# p2-003.net
KiCad netlist of a schematic drawn in EAGLE
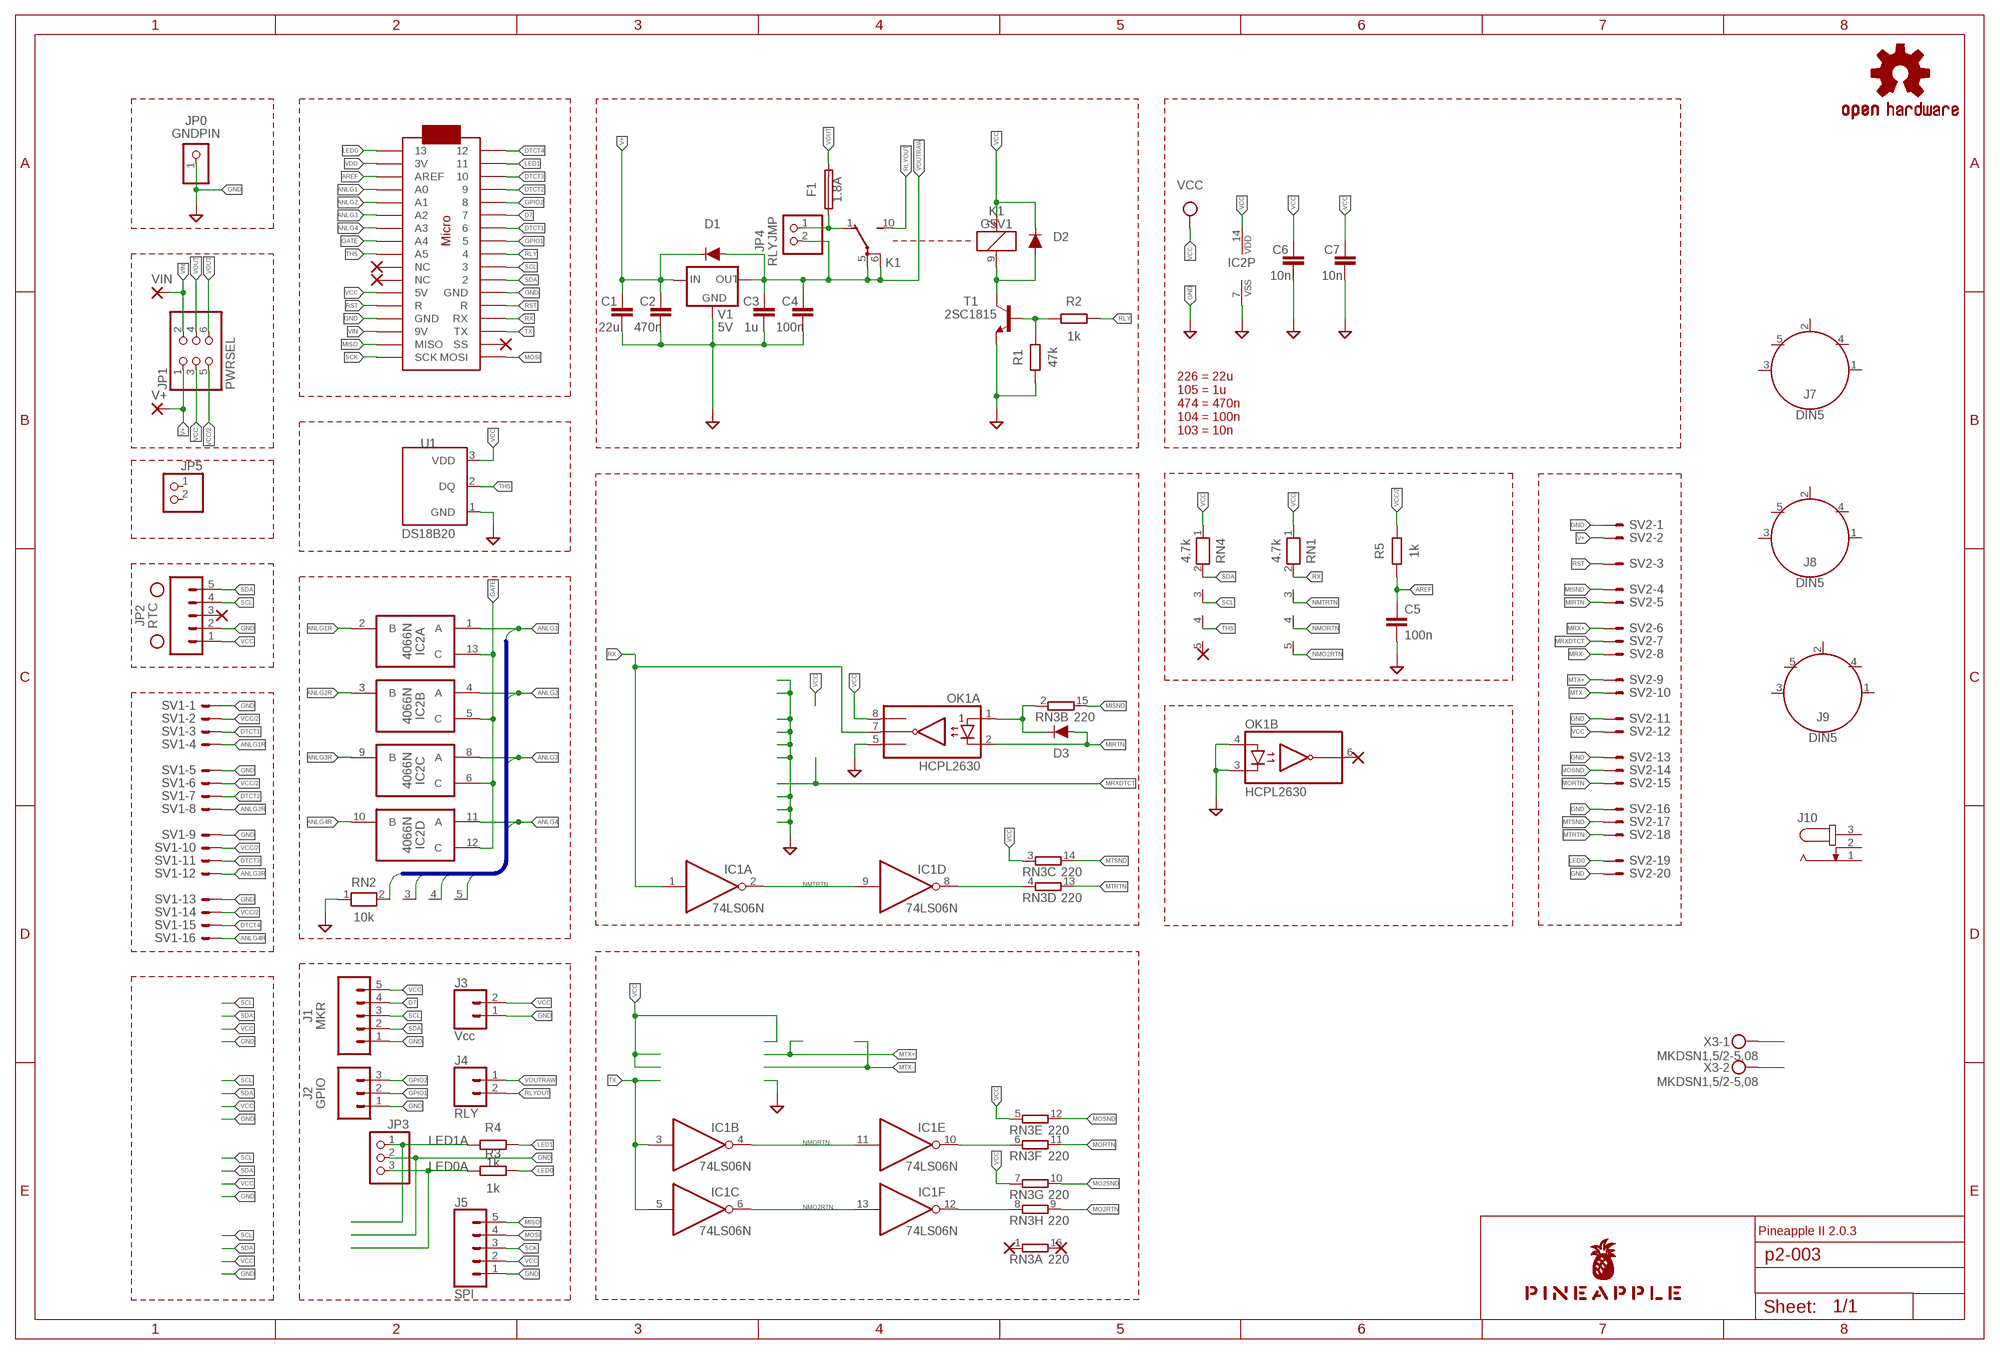
[diagram p0: schematic, sheet 1]

(export (version "E")
  (design (tool "Eeschema 10.0.6"))
  (components
    (comp (ref "C1")
      (value "22u")
      (footprint "eagle-import:C025-050X050")
      (libsource (lib "eagle-import") (part "C-EU025-050X050"))
    )
    (comp (ref "C2")
      (value "470n")
      (footprint "eagle-import:C050-024X044")
      (libsource (lib "eagle-import") (part "C-EU050-024X044"))
    )
    (comp (ref "C3")
      (value "1u")
      (footprint "eagle-import:C050-024X044")
      (libsource (lib "eagle-import") (part "C-EU050-024X044"))
    )
    (comp (ref "C4")
      (value "100n")
      (footprint "eagle-import:C025-024X044")
      (libsource (lib "eagle-import") (part "C-EU025-024X044"))
    )
    (comp (ref "C5")
      (value "100n")
      (footprint "eagle-import:C025-024X044")
      (libsource (lib "eagle-import") (part "C-EU025-024X044"))
    )
    (comp (ref "C6")
      (value "10n")
      (footprint "eagle-import:C025-024X044")
      (libsource (lib "eagle-import") (part "resistor_348_C-EU025-024X044"))
    )
    (comp (ref "C7")
      (value "10n")
      (footprint "eagle-import:C025-024X044")
      (libsource (lib "eagle-import") (part "resistor_348_C-EU025-024X044"))
    )
    (comp (ref "D1")
      (value "DIODE-1N4148")
      (footprint "eagle-import:DIODE-1N4148")
      (libsource (lib "eagle-import") (part "DIODE-1N4148"))
    )
    (comp (ref "D2")
      (value "DIODE-1N4148")
      (footprint "eagle-import:DIODE-1N4148")
      (libsource (lib "eagle-import") (part "DIODE-1N4148"))
    )
    (comp (ref "D3")
      (value "DIODE-1N4148")
      (footprint "eagle-import:DIODE-1N4148")
      (libsource (lib "eagle-import") (part "DIODE-1N4148"))
    )
    (comp (ref "F1")
      (value "1.8A")
      (footprint "eagle-import:TE5")
      (libsource (lib "eagle-import") (part "TE5"))
    )
    (comp (ref "H1")
      (value "STAND-OFF")
      (footprint "eagle-import:STAND-OFF")
      (libsource (lib "eagle-import") (part "STAND-OFF"))
    )
    (comp (ref "H2")
      (value "STAND-OFF")
      (footprint "eagle-import:STAND-OFF")
      (libsource (lib "eagle-import") (part "STAND-OFF"))
    )
    (comp (ref "IC1")
      (value "74LS06N")
      (footprint "eagle-import:DIL14")
      (libsource (lib "eagle-import") (part "7406NLS"))
    )
    (comp (ref "IC2")
      (value "4066N")
      (footprint "eagle-import:DIL14")
      (libsource (lib "eagle-import") (part "4066N"))
    )
    (comp (ref "J1")
      (value "MKR")
      (footprint "eagle-import:JST-5-PTH")
      (libsource (lib "eagle-import") (part "CONN_05JST"))
    )
    (comp (ref "J2")
      (value "GPIO")
      (footprint "eagle-import:JST-3-PTH")
      (libsource (lib "eagle-import") (part "CONN_03JST-PTH"))
    )
    (comp (ref "J3")
      (value "Vcc")
      (footprint "eagle-import:JST-2-PTH")
      (libsource (lib "eagle-import") (part "CONN_02JST-PTH-2"))
    )
    (comp (ref "J4")
      (value "RLY")
      (footprint "eagle-import:JST-2-SMD")
      (libsource (lib "eagle-import") (part "CONN_02-JST-2MM-SMT"))
    )
    (comp (ref "J5")
      (value "SPI")
      (footprint "eagle-import:JST-5-PTH-VERT")
      (libsource (lib "eagle-import") (part "CONN_05JST-VERT"))
    )
    (comp (ref "J7")
      (value "DIN5")
      (footprint "eagle-import:DIN5-RA-PTH")
      (libsource (lib "eagle-import") (part "DIN5"))
    )
    (comp (ref "J8")
      (value "DIN5")
      (footprint "eagle-import:DIN5-RA-PTH")
      (libsource (lib "eagle-import") (part "DIN5"))
    )
    (comp (ref "J9")
      (value "DIN5")
      (footprint "eagle-import:DIN5-RA-PTH")
      (libsource (lib "eagle-import") (part "DIN5"))
    )
    (comp (ref "J10")
      (value "JACK-PLUG0")
      (footprint "eagle-import:SPC4077")
      (libsource (lib "eagle-import") (part "JACK-PLUG0"))
    )
    (comp (ref "JP0")
      (value "GNDPIN")
      (footprint "eagle-import:1X01")
      (libsource (lib "eagle-import") (part "PINHD-1X1"))
    )
    (comp (ref "JP1")
      (value "PWRSEL")
      (footprint "eagle-import:2X03")
      (libsource (lib "eagle-import") (part "PINHD-2X3"))
    )
    (comp (ref "JP2")
      (value "RTC")
      (footprint "eagle-import:1X05")
      (libsource (lib "eagle-import") (part "CONN_05"))
    )
    (comp (ref "JP3")
      (value "PINHD-1X3")
      (footprint "eagle-import:1X03")
      (libsource (lib "eagle-import") (part "PINHD-1X3"))
    )
    (comp (ref "JP4")
      (value "RLYJMP")
      (footprint "eagle-import:1X02")
      (libsource (lib "eagle-import") (part "PINHD-1X2"))
    )
    (comp (ref "JP5")
      (value "PINHD-1X2")
      (footprint "eagle-import:1X02")
      (libsource (lib "eagle-import") (part "PINHD-1X2"))
    )
    (comp (ref "K1")
      (value "G5V1")
      (footprint "eagle-import:G5V1")
      (fields (field (name "MPN") "G5V-1-DC24"))
      (libsource (lib "eagle-import") (part "G5V1"))
    )
    (comp (ref "LOGO1")
      (value "OSHW-LOGOS-COPPER")
      (footprint "eagle-import:OSHW-LOGO-S_COPPER")
      (libsource (lib "eagle-import") (part "OSHW-LOGOS-COPPER"))
    )
    (comp (ref "MC1")
      (value "ARDUINOMICRO")
      (footprint "eagle-import:ARDUINOMICRO")
      (libsource (lib "eagle-import") (part "ARDUINOMICRO"))
    )
    (comp (ref "OK1")
      (value "HCPL2630")
      (footprint "eagle-import:DIL08")
      (fields (field (name "MF") "AGILENT TECHNOLOGIES") (field (name "MPN") "HCPL-2630-000E"))
      (libsource (lib "eagle-import") (part "HCPL2630"))
    )
    (comp (ref "R1")
      (value "47k")
      (footprint "eagle-import:0204_5")
      (libsource (lib "eagle-import") (part "R-EU_0204/5"))
    )
    (comp (ref "R2")
      (value "1k")
      (footprint "eagle-import:0204_5")
      (libsource (lib "eagle-import") (part "R-EU_0204/5"))
    )
    (comp (ref "R3")
      (value "1k")
      (footprint "eagle-import:0204_5")
      (libsource (lib "eagle-import") (part "R-EU_0204/5"))
    )
    (comp (ref "R4")
      (value "1k")
      (footprint "eagle-import:0204_5")
      (libsource (lib "eagle-import") (part "R-EU_0204/5"))
    )
    (comp (ref "R5")
      (value "1k")
      (footprint "eagle-import:0204_5")
      (libsource (lib "eagle-import") (part "R-EU_0204/5"))
    )
    (comp (ref "RN1")
      (value "4.7k")
      (footprint "eagle-import:RN-5")
      (libsource (lib "eagle-import") (part "RN04"))
    )
    (comp (ref "RN2")
      (value "10k")
      (footprint "eagle-import:RN-5")
      (libsource (lib "eagle-import") (part "RN04"))
    )
    (comp (ref "RN3")
      (value "220")
      (footprint "eagle-import:DIL16")
      (libsource (lib "eagle-import") (part "8R-N"))
    )
    (comp (ref "RN4")
      (value "4.7k")
      (footprint "eagle-import:RN-5")
      (libsource (lib "eagle-import") (part "RN04"))
    )
    (comp (ref "SV1")
      (value "ML16LE")
      (footprint "eagle-import:ML16L")
      (libsource (lib "eagle-import") (part "ML16LE"))
    )
    (comp (ref "SV2")
      (value "ML20LE")
      (footprint "eagle-import:ML20L")
      (libsource (lib "eagle-import") (part "ML20LE"))
    )
    (comp (ref "T1")
      (value "2SC1815")
      (footprint "eagle-import:TO92-ECB")
      (libsource (lib "eagle-import") (part "2SC1815"))
    )
    (comp (ref "U$1")
      (value "PINEAPPLE450_SILK")
      (footprint "eagle-import:PINEAPPLE450_SILK")
      (libsource (lib "eagle-import") (part "PINEAPPLE450_SILK"))
    )
    (comp (ref "U1")
      (value "DS18B20")
      (footprint "eagle-import:TO-92-AMMO")
      (libsource (lib "eagle-import") (part "DS18B20"))
    )
    (comp (ref "V+")
      (value "SMD2")
      (footprint "eagle-import:SMD1,27-2,54")
      (libsource (lib "eagle-import") (part "SMD2"))
    )
    (comp (ref "V1")
      (value "5V")
      (footprint "eagle-import:78XXL")
      (libsource (lib "eagle-import") (part "78XXL"))
    )
    (comp (ref "VIN")
      (value "SMD2")
      (footprint "eagle-import:SMD1,27-2,54")
      (libsource (lib "eagle-import") (part "SMD2"))
    )
    (comp (ref "X3")
      (value "MKDSN1,5/2-5,08")
      (footprint "eagle-import:MKDSN1,5_2-5,08")
      (libsource (lib "eagle-import") (part "MKDSN1,5/2-5,08"))
    )
  )
  (nets
    (net (code "1") (name "/LED0A") (class "Default")
      (node (ref "JP3") (pin "3") (pinfunction "3_3") (pintype "passive"))
      (node (ref "R3") (pin "1") (pinfunction "1_1") (pintype "passive"))
    )
    (net (code "2") (name "/LED1A") (class "Default")
      (node (ref "JP3") (pin "1") (pinfunction "1_1") (pintype "passive"))
      (node (ref "R4") (pin "1") (pinfunction "1_1") (pintype "passive"))
    )
    (net (code "3") (name "ANLG1") (class "Default")
      (node (ref "IC2") (pin "1") (pinfunction "A_1") (pintype "tri_state"))
      (node (ref "MC1") (pin "P$31") (pinfunction "A0_P$31") (pintype "bidirectional"))
      (node (ref "RN2") (pin "2") (pinfunction "2_2") (pintype "passive"))
    )
    (net (code "4") (name "ANLG1R") (class "Default")
      (node (ref "IC2") (pin "2") (pinfunction "B_2") (pintype "tri_state"))
      (node (ref "SV1") (pin "4") (pinfunction "S_4") (pintype "passive"))
    )
    (net (code "5") (name "ANLG2") (class "Default")
      (node (ref "IC2") (pin "4") (pinfunction "A_4") (pintype "tri_state"))
      (node (ref "MC1") (pin "P$30") (pinfunction "A1_P$30") (pintype "bidirectional"))
      (node (ref "RN2") (pin "3") (pinfunction "3_3") (pintype "passive"))
    )
    (net (code "6") (name "ANLG2R") (class "Default")
      (node (ref "IC2") (pin "3") (pinfunction "B_3") (pintype "tri_state"))
      (node (ref "SV1") (pin "8") (pinfunction "S_8") (pintype "passive"))
    )
    (net (code "7") (name "ANLG3") (class "Default")
      (node (ref "IC2") (pin "8") (pinfunction "A_8") (pintype "tri_state"))
      (node (ref "MC1") (pin "P$29") (pinfunction "A2_P$29") (pintype "bidirectional"))
      (node (ref "RN2") (pin "4") (pinfunction "4_4") (pintype "passive"))
    )
    (net (code "8") (name "ANLG3R") (class "Default")
      (node (ref "IC2") (pin "9") (pinfunction "B_9") (pintype "tri_state"))
      (node (ref "SV1") (pin "12") (pinfunction "S_12") (pintype "passive"))
    )
    (net (code "9") (name "ANLG4") (class "Default")
      (node (ref "IC2") (pin "11") (pinfunction "A_11") (pintype "tri_state"))
      (node (ref "MC1") (pin "P$28") (pinfunction "A3_P$28") (pintype "bidirectional"))
      (node (ref "RN2") (pin "5") (pinfunction "5_5") (pintype "passive"))
    )
    (net (code "10") (name "ANLG4R") (class "Default")
      (node (ref "IC2") (pin "10") (pinfunction "B_10") (pintype "tri_state"))
      (node (ref "SV1") (pin "16") (pinfunction "S_16") (pintype "passive"))
    )
    (net (code "11") (name "AREF") (class "Default")
      (node (ref "C5") (pin "1") (pinfunction "1_1") (pintype "passive"))
      (node (ref "MC1") (pin "P$32") (pinfunction "AREF_P$32") (pintype "bidirectional"))
      (node (ref "R5") (pin "1") (pinfunction "1_1") (pintype "passive"))
    )
    (net (code "12") (name "D7") (class "Default")
      (node (ref "J1") (pin "4") (pinfunction "4_4") (pintype "passive"))
      (node (ref "MC1") (pin "P$6") (pinfunction "7_P$6") (pintype "bidirectional"))
    )
    (net (code "13") (name "DTCT1") (class "Default")
      (node (ref "MC1") (pin "P$7") (pinfunction "6_P$7") (pintype "bidirectional"))
      (node (ref "SV1") (pin "3") (pinfunction "S_3") (pintype "passive"))
    )
    (net (code "14") (name "DTCT2") (class "Default")
      (node (ref "MC1") (pin "P$4") (pinfunction "9_P$4") (pintype "bidirectional"))
      (node (ref "SV1") (pin "7") (pinfunction "S_7") (pintype "passive"))
    )
    (net (code "15") (name "DTCT3") (class "Default")
      (node (ref "MC1") (pin "P$3") (pinfunction "10_P$3") (pintype "bidirectional"))
      (node (ref "SV1") (pin "11") (pinfunction "S_11") (pintype "passive"))
    )
    (net (code "16") (name "DTCT4") (class "Default")
      (node (ref "MC1") (pin "P$1") (pinfunction "12_P$1") (pintype "bidirectional"))
      (node (ref "SV1") (pin "15") (pinfunction "S_15") (pintype "passive"))
    )
    (net (code "17") (name "GATE") (class "Default")
      (node (ref "IC2") (pin "12") (pinfunction "C_12") (pintype "input"))
      (node (ref "IC2") (pin "13") (pinfunction "C_13") (pintype "input"))
      (node (ref "IC2") (pin "5") (pinfunction "C_5") (pintype "input"))
      (node (ref "IC2") (pin "6") (pinfunction "C_6") (pintype "input"))
      (node (ref "MC1") (pin "P$27") (pinfunction "A4_P$27") (pintype "bidirectional"))
    )
    (net (code "18") (name "GND") (class "Default")
      (node (ref "C1") (pin "2") (pinfunction "2_2") (pintype "passive"))
      (node (ref "C2") (pin "2") (pinfunction "2_2") (pintype "passive"))
      (node (ref "C3") (pin "2") (pinfunction "2_2") (pintype "passive"))
      (node (ref "C4") (pin "2") (pinfunction "2_2") (pintype "passive"))
      (node (ref "C5") (pin "2") (pinfunction "2_2") (pintype "passive"))
      (node (ref "C6") (pin "2") (pinfunction "2_2") (pintype "passive"))
      (node (ref "C7") (pin "2") (pinfunction "2_2") (pintype "passive"))
      (node (ref "IC2") (pin "7") (pinfunction "VSS_7") (pintype "power_in"))
      (node (ref "J1") (pin "1") (pinfunction "1_1") (pintype "passive"))
      (node (ref "J2") (pin "1") (pinfunction "1_1") (pintype "passive"))
      (node (ref "J3") (pin "1") (pinfunction "1_1") (pintype "passive"))
      (node (ref "J5") (pin "1") (pinfunction "1_1") (pintype "passive"))
      (node (ref "JP0") (pin "1") (pinfunction "1_1") (pintype "passive"))
      (node (ref "JP2") (pin "2") (pinfunction "2_2") (pintype "passive"))
      (node (ref "JP3") (pin "2") (pinfunction "2_2") (pintype "passive"))
      (node (ref "MC1") (pin "P$12") (pinfunction "GND_P$12") (pintype "bidirectional"))
      (node (ref "MC1") (pin "P$21") (pinfunction "GND_P$21") (pintype "bidirectional"))
      (node (ref "OK1") (pin "3") (pinfunction "C2_3") (pintype "passive"))
      (node (ref "OK1") (pin "4") (pinfunction "A2_4") (pintype "passive"))
      (node (ref "OK1") (pin "5") (pinfunction "GND_5") (pintype "passive"))
      (node (ref "R1") (pin "1") (pinfunction "1_1") (pintype "passive"))
      (node (ref "RN2") (pin "1") (pinfunction "1_1") (pintype "passive"))
      (node (ref "SV1") (pin "1") (pinfunction "S_1") (pintype "passive"))
      (node (ref "SV1") (pin "13") (pinfunction "S_13") (pintype "passive"))
      (node (ref "SV1") (pin "5") (pinfunction "S_5") (pintype "passive"))
      (node (ref "SV1") (pin "9") (pinfunction "S_9") (pintype "passive"))
      (node (ref "SV2") (pin "1") (pinfunction "S_1") (pintype "passive"))
      (node (ref "SV2") (pin "11") (pinfunction "S_11") (pintype "passive"))
      (node (ref "SV2") (pin "13") (pinfunction "S_13") (pintype "passive"))
      (node (ref "SV2") (pin "16") (pinfunction "S_16") (pintype "passive"))
      (node (ref "SV2") (pin "20") (pinfunction "S_20") (pintype "passive"))
      (node (ref "T1") (pin "E") (pinfunction "E_E") (pintype "passive"))
      (node (ref "U1") (pin "1") (pinfunction "GND_1") (pintype "power_in"))
      (node (ref "V1") (pin "GND") (pinfunction "GND_GND") (pintype "input"))
      (node (ref "X3") (pin "1") (pinfunction "KL_1") (pintype "passive"))
    )
    (net (code "19") (name "GPIO1") (class "Default")
      (node (ref "J2") (pin "2") (pinfunction "2_2") (pintype "passive"))
      (node (ref "MC1") (pin "P$8") (pinfunction "5_P$8") (pintype "bidirectional"))
    )
    (net (code "20") (name "GPIO2") (class "Default")
      (node (ref "J2") (pin "3") (pinfunction "3_3") (pintype "passive"))
      (node (ref "MC1") (pin "P$5") (pinfunction "8_P$5") (pintype "bidirectional"))
    )
    (net (code "21") (name "LED0") (class "Default")
      (node (ref "MC1") (pin "P$34") (pinfunction "13_P$34") (pintype "bidirectional"))
      (node (ref "R3") (pin "2") (pinfunction "2_2") (pintype "passive"))
      (node (ref "SV2") (pin "19") (pinfunction "S_19") (pintype "passive"))
    )
    (net (code "22") (name "LED1") (class "Default")
      (node (ref "MC1") (pin "P$2") (pinfunction "11_P$2") (pintype "bidirectional"))
      (node (ref "R4") (pin "2") (pinfunction "2_2") (pintype "passive"))
    )
    (net (code "23") (name "MIRTN") (class "Default")
      (node (ref "D3") (pin "A") (pinfunction "A_A") (pintype "passive"))
      (node (ref "OK1") (pin "2") (pinfunction "C1_2") (pintype "passive"))
      (node (ref "SV2") (pin "5") (pinfunction "S_5") (pintype "passive"))
    )
    (net (code "24") (name "MISND") (class "Default")
      (node (ref "RN3") (pin "15") (pinfunction "2_15") (pintype "passive"))
      (node (ref "SV2") (pin "4") (pinfunction "S_4") (pintype "passive"))
    )
    (net (code "25") (name "MISO") (class "Default")
      (node (ref "J5") (pin "5") (pinfunction "5_5") (pintype "passive"))
      (node (ref "MC1") (pin "P$19") (pinfunction "MISO_P$19") (pintype "bidirectional"))
    )
    (net (code "26") (name "MO2RTN") (class "Default")
      (node (ref "RN3") (pin "9") (pinfunction "2_9") (pintype "passive"))
    )
    (net (code "27") (name "MO2SND") (class "Default")
      (node (ref "RN3") (pin "10") (pinfunction "2_10") (pintype "passive"))
    )
    (net (code "28") (name "MORTN") (class "Default")
      (node (ref "RN3") (pin "11") (pinfunction "2_11") (pintype "passive"))
      (node (ref "SV2") (pin "15") (pinfunction "S_15") (pintype "passive"))
    )
    (net (code "29") (name "MOSI") (class "Default")
      (node (ref "J5") (pin "4") (pinfunction "4_4") (pintype "passive"))
      (node (ref "MC1") (pin "P$17") (pinfunction "MOSI_P$17") (pintype "bidirectional"))
    )
    (net (code "30") (name "MOSND") (class "Default")
      (node (ref "RN3") (pin "12") (pinfunction "2_12") (pintype "passive"))
      (node (ref "SV2") (pin "14") (pinfunction "S_14") (pintype "passive"))
    )
    (net (code "31") (name "MRX+") (class "Default")
      (node (ref "SV2") (pin "6") (pinfunction "S_6") (pintype "passive"))
    )
    (net (code "32") (name "MRX-") (class "Default")
      (node (ref "SV2") (pin "8") (pinfunction "S_8") (pintype "passive"))
    )
    (net (code "33") (name "MRXDTCT") (class "Default")
      (node (ref "SV2") (pin "7") (pinfunction "S_7") (pintype "passive"))
    )
    (net (code "34") (name "MTRTN") (class "Default")
      (node (ref "RN3") (pin "13") (pinfunction "2_13") (pintype "passive"))
      (node (ref "SV2") (pin "18") (pinfunction "S_18") (pintype "passive"))
    )
    (net (code "35") (name "MTSND") (class "Default")
      (node (ref "RN3") (pin "14") (pinfunction "2_14") (pintype "passive"))
      (node (ref "SV2") (pin "17") (pinfunction "S_17") (pintype "passive"))
    )
    (net (code "36") (name "MTX+") (class "Default")
      (node (ref "SV2") (pin "9") (pinfunction "S_9") (pintype "passive"))
    )
    (net (code "37") (name "MTX-") (class "Default")
      (node (ref "SV2") (pin "10") (pinfunction "S_10") (pintype "passive"))
    )
    (net (code "38") (name "NMO2RTN") (class "Default")
      (node (ref "IC1") (pin "13") (pinfunction "I_13") (pintype "input"))
      (node (ref "IC1") (pin "6") (pinfunction "O_6") (pintype "open_collector"))
      (node (ref "RN1") (pin "5") (pinfunction "5_5") (pintype "passive"))
    )
    (net (code "39") (name "NMORTN") (class "Default")
      (node (ref "IC1") (pin "11") (pinfunction "I_11") (pintype "input"))
      (node (ref "IC1") (pin "4") (pinfunction "O_4") (pintype "open_collector"))
      (node (ref "RN1") (pin "4") (pinfunction "4_4") (pintype "passive"))
    )
    (net (code "40") (name "NMTRTN") (class "Default")
      (node (ref "IC1") (pin "2") (pinfunction "O_2") (pintype "open_collector"))
      (node (ref "IC1") (pin "9") (pinfunction "I_9") (pintype "input"))
      (node (ref "RN1") (pin "3") (pinfunction "3_3") (pintype "passive"))
    )
    (net (code "41") (name "Net-(IC1D-O)") (class "Default")
      (node (ref "IC1") (pin "8") (pinfunction "O_8") (pintype "open_collector"))
      (node (ref "RN3") (pin "4") (pinfunction "1_4") (pintype "passive"))
    )
    (net (code "42") (name "Net-(IC1E-O)") (class "Default")
      (node (ref "IC1") (pin "10") (pinfunction "O_10") (pintype "open_collector"))
      (node (ref "RN3") (pin "6") (pinfunction "1_6") (pintype "passive"))
    )
    (net (code "43") (name "Net-(IC1F-O)") (class "Default")
      (node (ref "IC1") (pin "12") (pinfunction "O_12") (pintype "open_collector"))
      (node (ref "RN3") (pin "8") (pinfunction "1_8") (pintype "passive"))
    )
    (net (code "44") (name "Net-(K1A-2)") (class "Default")
      (node (ref "D2") (pin "A") (pinfunction "A_A") (pintype "passive"))
      (node (ref "K1") (pin "9") (pinfunction "2_9") (pintype "passive"))
      (node (ref "T1") (pin "C") (pinfunction "C_C") (pintype "passive"))
    )
    (net (code "45") (name "Net-(K1B-O)") (class "Default")
      (node (ref "F1") (pin "1") (pinfunction "1_1") (pintype "passive"))
      (node (ref "JP4") (pin "1") (pinfunction "1_1") (pintype "passive"))
      (node (ref "K1") (pin "1") (pinfunction "O_1") (pintype "passive"))
    )
    (net (code "46") (name "Net-(OK1A-A1)") (class "Default")
      (node (ref "D3") (pin "C") (pinfunction "C_C") (pintype "passive"))
      (node (ref "OK1") (pin "1") (pinfunction "A1_1") (pintype "passive"))
      (node (ref "RN3") (pin "2") (pinfunction "1_2") (pintype "passive"))
    )
    (net (code "47") (name "Net-(R1-Pad2)") (class "Default")
      (node (ref "R1") (pin "2") (pinfunction "2_2") (pintype "passive"))
      (node (ref "R2") (pin "1") (pinfunction "1_1") (pintype "passive"))
      (node (ref "T1") (pin "B") (pinfunction "B_B") (pintype "passive"))
    )
    (net (code "48") (name "RLY") (class "Default")
      (node (ref "MC1") (pin "P$9") (pinfunction "4_P$9") (pintype "bidirectional"))
      (node (ref "R2") (pin "2") (pinfunction "2_2") (pintype "passive"))
    )
    (net (code "49") (name "RLYOUT") (class "Default")
      (node (ref "J4") (pin "2") (pinfunction "1_2") (pintype "passive"))
      (node (ref "K1") (pin "10") (pinfunction "S_10") (pintype "passive"))
    )
    (net (code "50") (name "RST") (class "Default")
      (node (ref "MC1") (pin "P$13") (pinfunction "R_P$13") (pintype "bidirectional"))
      (node (ref "MC1") (pin "P$22") (pinfunction "R_P$22") (pintype "bidirectional"))
      (node (ref "SV2") (pin "3") (pinfunction "S_3") (pintype "passive"))
    )
    (net (code "51") (name "RX") (class "Default")
      (node (ref "IC1") (pin "1") (pinfunction "I_1") (pintype "input"))
      (node (ref "MC1") (pin "P$14") (pinfunction "RX_P$14") (pintype "bidirectional"))
      (node (ref "OK1") (pin "7") (pinfunction "VO1_7") (pintype "passive"))
      (node (ref "RN1") (pin "2") (pinfunction "2_2") (pintype "passive"))
    )
    (net (code "52") (name "SCK") (class "Default")
      (node (ref "J5") (pin "3") (pinfunction "3_3") (pintype "passive"))
      (node (ref "MC1") (pin "P$18") (pinfunction "SCK_P$18") (pintype "bidirectional"))
    )
    (net (code "53") (name "SCL") (class "Default")
      (node (ref "J1") (pin "3") (pinfunction "3_3") (pintype "passive"))
      (node (ref "JP2") (pin "4") (pinfunction "4_4") (pintype "passive"))
      (node (ref "MC1") (pin "P$10") (pinfunction "3_P$10") (pintype "bidirectional"))
      (node (ref "RN4") (pin "3") (pinfunction "3_3") (pintype "passive"))
    )
    (net (code "54") (name "SDA") (class "Default")
      (node (ref "J1") (pin "2") (pinfunction "2_2") (pintype "passive"))
      (node (ref "JP2") (pin "5") (pinfunction "5_5") (pintype "passive"))
      (node (ref "MC1") (pin "P$11") (pinfunction "2_P$11") (pintype "bidirectional"))
      (node (ref "RN4") (pin "2") (pinfunction "2_2") (pintype "passive"))
    )
    (net (code "55") (name "THS") (class "Default")
      (node (ref "MC1") (pin "P$26") (pinfunction "A5_P$26") (pintype "bidirectional"))
      (node (ref "RN4") (pin "4") (pinfunction "4_4") (pintype "passive"))
      (node (ref "U1") (pin "2") (pinfunction "DQ_2") (pintype "bidirectional"))
    )
    (net (code "56") (name "TX") (class "Default")
      (node (ref "IC1") (pin "3") (pinfunction "I_3") (pintype "input"))
      (node (ref "IC1") (pin "5") (pinfunction "I_5") (pintype "input"))
      (node (ref "MC1") (pin "P$15") (pinfunction "TX_P$15") (pintype "bidirectional"))
    )
    (net (code "57") (name "V+") (class "Default")
      (node (ref "C1") (pin "1") (pinfunction "1_1") (pintype "passive"))
      (node (ref "C2") (pin "1") (pinfunction "1_1") (pintype "passive"))
      (node (ref "D1") (pin "C") (pinfunction "C_C") (pintype "passive"))
      (node (ref "JP1") (pin "1") (pinfunction "1_1") (pintype "passive"))
      (node (ref "SV2") (pin "2") (pinfunction "S_2") (pintype "passive"))
      (node (ref "V+") (pin "1") (pinfunction "P_1") (pintype "passive"))
      (node (ref "V1") (pin "IN") (pinfunction "IN_IN") (pintype "input"))
      (node (ref "X3") (pin "2") (pinfunction "KL_2") (pintype "passive"))
    )
    (net (code "58") (name "VCC") (class "Default")
      (node (ref "C6") (pin "1") (pinfunction "1_1") (pintype "passive"))
      (node (ref "C7") (pin "1") (pinfunction "1_1") (pintype "passive"))
      (node (ref "D2") (pin "C") (pinfunction "C_C") (pintype "passive"))
      (node (ref "IC2") (pin "14") (pinfunction "VDD_14") (pintype "power_in"))
      (node (ref "J1") (pin "5") (pinfunction "5_5") (pintype "passive"))
      (node (ref "J3") (pin "2") (pinfunction "2_2") (pintype "passive"))
      (node (ref "J5") (pin "2") (pinfunction "2_2") (pintype "passive"))
      (node (ref "JP1") (pin "3") (pinfunction "3_3") (pintype "passive"))
      (node (ref "JP2") (pin "1") (pinfunction "1_1") (pintype "passive"))
      (node (ref "K1") (pin "2") (pinfunction "1_2") (pintype "passive"))
      (node (ref "MC1") (pin "P$23") (pinfunction "5V_P$23") (pintype "bidirectional"))
      (node (ref "OK1") (pin "8") (pinfunction "VCC_8") (pintype "passive"))
      (node (ref "RN1") (pin "1") (pinfunction "1_1") (pintype "passive"))
      (node (ref "RN3") (pin "3") (pinfunction "1_3") (pintype "passive"))
      (node (ref "RN3") (pin "5") (pinfunction "1_5") (pintype "passive"))
      (node (ref "RN3") (pin "7") (pinfunction "1_7") (pintype "passive"))
      (node (ref "RN4") (pin "1") (pinfunction "1_1") (pintype "passive"))
      (node (ref "SV2") (pin "12") (pinfunction "S_12") (pintype "passive"))
      (node (ref "U1") (pin "3") (pinfunction "VDD_3") (pintype "power_in"))
    )
    (net (code "59") (name "VCC{slash}2") (class "Default")
      (node (ref "JP1") (pin "5") (pinfunction "5_5") (pintype "passive"))
      (node (ref "R5") (pin "2") (pinfunction "2_2") (pintype "passive"))
      (node (ref "SV1") (pin "10") (pinfunction "S_10") (pintype "passive"))
      (node (ref "SV1") (pin "14") (pinfunction "S_14") (pintype "passive"))
      (node (ref "SV1") (pin "2") (pinfunction "S_2") (pintype "passive"))
      (node (ref "SV1") (pin "6") (pinfunction "S_6") (pintype "passive"))
    )
    (net (code "60") (name "VDD") (class "Default")
      (node (ref "MC1") (pin "P$33") (pinfunction "3V_P$33") (pintype "bidirectional"))
    )
    (net (code "61") (name "VIN") (class "Default")
      (node (ref "JP1") (pin "2") (pinfunction "2_2") (pintype "passive"))
      (node (ref "MC1") (pin "P$20") (pinfunction "9V_P$20") (pintype "bidirectional"))
      (node (ref "VIN") (pin "1") (pinfunction "P_1") (pintype "passive"))
    )
    (net (code "62") (name "VOUT") (class "Default")
      (node (ref "F1") (pin "2") (pinfunction "2_2") (pintype "passive"))
      (node (ref "JP1") (pin "4") (pinfunction "4_4") (pintype "passive"))
      (node (ref "JP1") (pin "6") (pinfunction "6_6") (pintype "passive"))
    )
    (net (code "63") (name "VOUTRAW") (class "Default")
      (node (ref "C3") (pin "1") (pinfunction "1_1") (pintype "passive"))
      (node (ref "C4") (pin "1") (pinfunction "1_1") (pintype "passive"))
      (node (ref "D1") (pin "A") (pinfunction "A_A") (pintype "passive"))
      (node (ref "J4") (pin "1") (pinfunction "2_1") (pintype "passive"))
      (node (ref "JP4") (pin "2") (pinfunction "2_2") (pintype "passive"))
      (node (ref "K1") (pin "5") (pinfunction "P_5") (pintype "passive"))
      (node (ref "K1") (pin "6") (pinfunction "P_6") (pintype "passive"))
      (node (ref "V1") (pin "OUT") (pinfunction "OUT_OUT") (pintype "passive"))
    )
    (net (code "64") (name "unconnected-(J7-Pad1)") (class "Default")
      (node (ref "J7") (pin "1") (pinfunction "1_1") (pintype "bidirectional"))
    )
    (net (code "65") (name "unconnected-(J7-Pad2)") (class "Default")
      (node (ref "J7") (pin "2") (pinfunction "2_2") (pintype "bidirectional"))
    )
    (net (code "66") (name "unconnected-(J7-Pad3)") (class "Default")
      (node (ref "J7") (pin "3") (pinfunction "3_3") (pintype "bidirectional"))
    )
    (net (code "67") (name "unconnected-(J7-Pad4)") (class "Default")
      (node (ref "J7") (pin "4") (pinfunction "4_4") (pintype "bidirectional"))
    )
    (net (code "68") (name "unconnected-(J7-Pad5)") (class "Default")
      (node (ref "J7") (pin "5") (pinfunction "5_5") (pintype "bidirectional"))
    )
    (net (code "69") (name "unconnected-(J8-Pad1)") (class "Default")
      (node (ref "J8") (pin "1") (pinfunction "1_1") (pintype "bidirectional"))
    )
    (net (code "70") (name "unconnected-(J8-Pad2)") (class "Default")
      (node (ref "J8") (pin "2") (pinfunction "2_2") (pintype "bidirectional"))
    )
    (net (code "71") (name "unconnected-(J8-Pad3)") (class "Default")
      (node (ref "J8") (pin "3") (pinfunction "3_3") (pintype "bidirectional"))
    )
    (net (code "72") (name "unconnected-(J8-Pad4)") (class "Default")
      (node (ref "J8") (pin "4") (pinfunction "4_4") (pintype "bidirectional"))
    )
    (net (code "73") (name "unconnected-(J8-Pad5)") (class "Default")
      (node (ref "J8") (pin "5") (pinfunction "5_5") (pintype "bidirectional"))
    )
    (net (code "74") (name "unconnected-(J9-Pad1)") (class "Default")
      (node (ref "J9") (pin "1") (pinfunction "1_1") (pintype "bidirectional"))
    )
    (net (code "75") (name "unconnected-(J9-Pad2)") (class "Default")
      (node (ref "J9") (pin "2") (pinfunction "2_2") (pintype "bidirectional"))
    )
    (net (code "76") (name "unconnected-(J9-Pad3)") (class "Default")
      (node (ref "J9") (pin "3") (pinfunction "3_3") (pintype "bidirectional"))
    )
    (net (code "77") (name "unconnected-(J9-Pad4)") (class "Default")
      (node (ref "J9") (pin "4") (pinfunction "4_4") (pintype "bidirectional"))
    )
    (net (code "78") (name "unconnected-(J9-Pad5)") (class "Default")
      (node (ref "J9") (pin "5") (pinfunction "5_5") (pintype "bidirectional"))
    )
    (net (code "79") (name "unconnected-(J10-Pad1)") (class "Default")
      (node (ref "J10") (pin "1") (pinfunction "1_1") (pintype "passive"))
    )
    (net (code "80") (name "unconnected-(J10-Pad2)") (class "Default")
      (node (ref "J10") (pin "2") (pinfunction "2_2") (pintype "passive"))
    )
    (net (code "81") (name "unconnected-(J10-Pad3)") (class "Default")
      (node (ref "J10") (pin "3") (pinfunction "3_3") (pintype "passive"))
    )
    (net (code "82") (name "unconnected-(JP2-Pad3)") (class "Default")
      (node (ref "JP2") (pin "3") (pinfunction "3_3") (pintype "passive"))
    )
    (net (code "83") (name "unconnected-(JP5-Pad1)") (class "Default")
      (node (ref "JP5") (pin "1") (pinfunction "1_1") (pintype "passive"))
    )
    (net (code "84") (name "unconnected-(JP5-Pad2)") (class "Default")
      (node (ref "JP5") (pin "2") (pinfunction "2_2") (pintype "passive"))
    )
    (net (code "85") (name "unconnected-(MC1-NC-PadP$24)") (class "Default")
      (node (ref "MC1") (pin "P$24") (pinfunction "NC_P$24") (pintype "bidirectional"))
    )
    (net (code "86") (name "unconnected-(MC1-NC-PadP$25)") (class "Default")
      (node (ref "MC1") (pin "P$25") (pinfunction "NC_P$25") (pintype "bidirectional"))
    )
    (net (code "87") (name "unconnected-(MC1-SS-PadP$16)") (class "Default")
      (node (ref "MC1") (pin "P$16") (pinfunction "SS_P$16") (pintype "bidirectional"))
    )
    (net (code "88") (name "unconnected-(OK1B-VO2-Pad6)") (class "Default")
      (node (ref "OK1") (pin "6") (pinfunction "VO2_6") (pintype "passive"))
    )
    (net (code "89") (name "unconnected-(RN3-Pad1)") (class "Default")
      (node (ref "RN3") (pin "1") (pinfunction "1_1") (pintype "passive"))
    )
    (net (code "90") (name "unconnected-(RN3A-2-Pad16)") (class "Default")
      (node (ref "RN3") (pin "16") (pinfunction "2_16") (pintype "passive"))
    )
    (net (code "91") (name "unconnected-(RN4-Pad5)") (class "Default")
      (node (ref "RN4") (pin "5") (pinfunction "5_5") (pintype "passive"))
    )
  )
)
